# antennenanalysator_m4_1.net
KiCad netlist of a schematic drawn in EAGLE
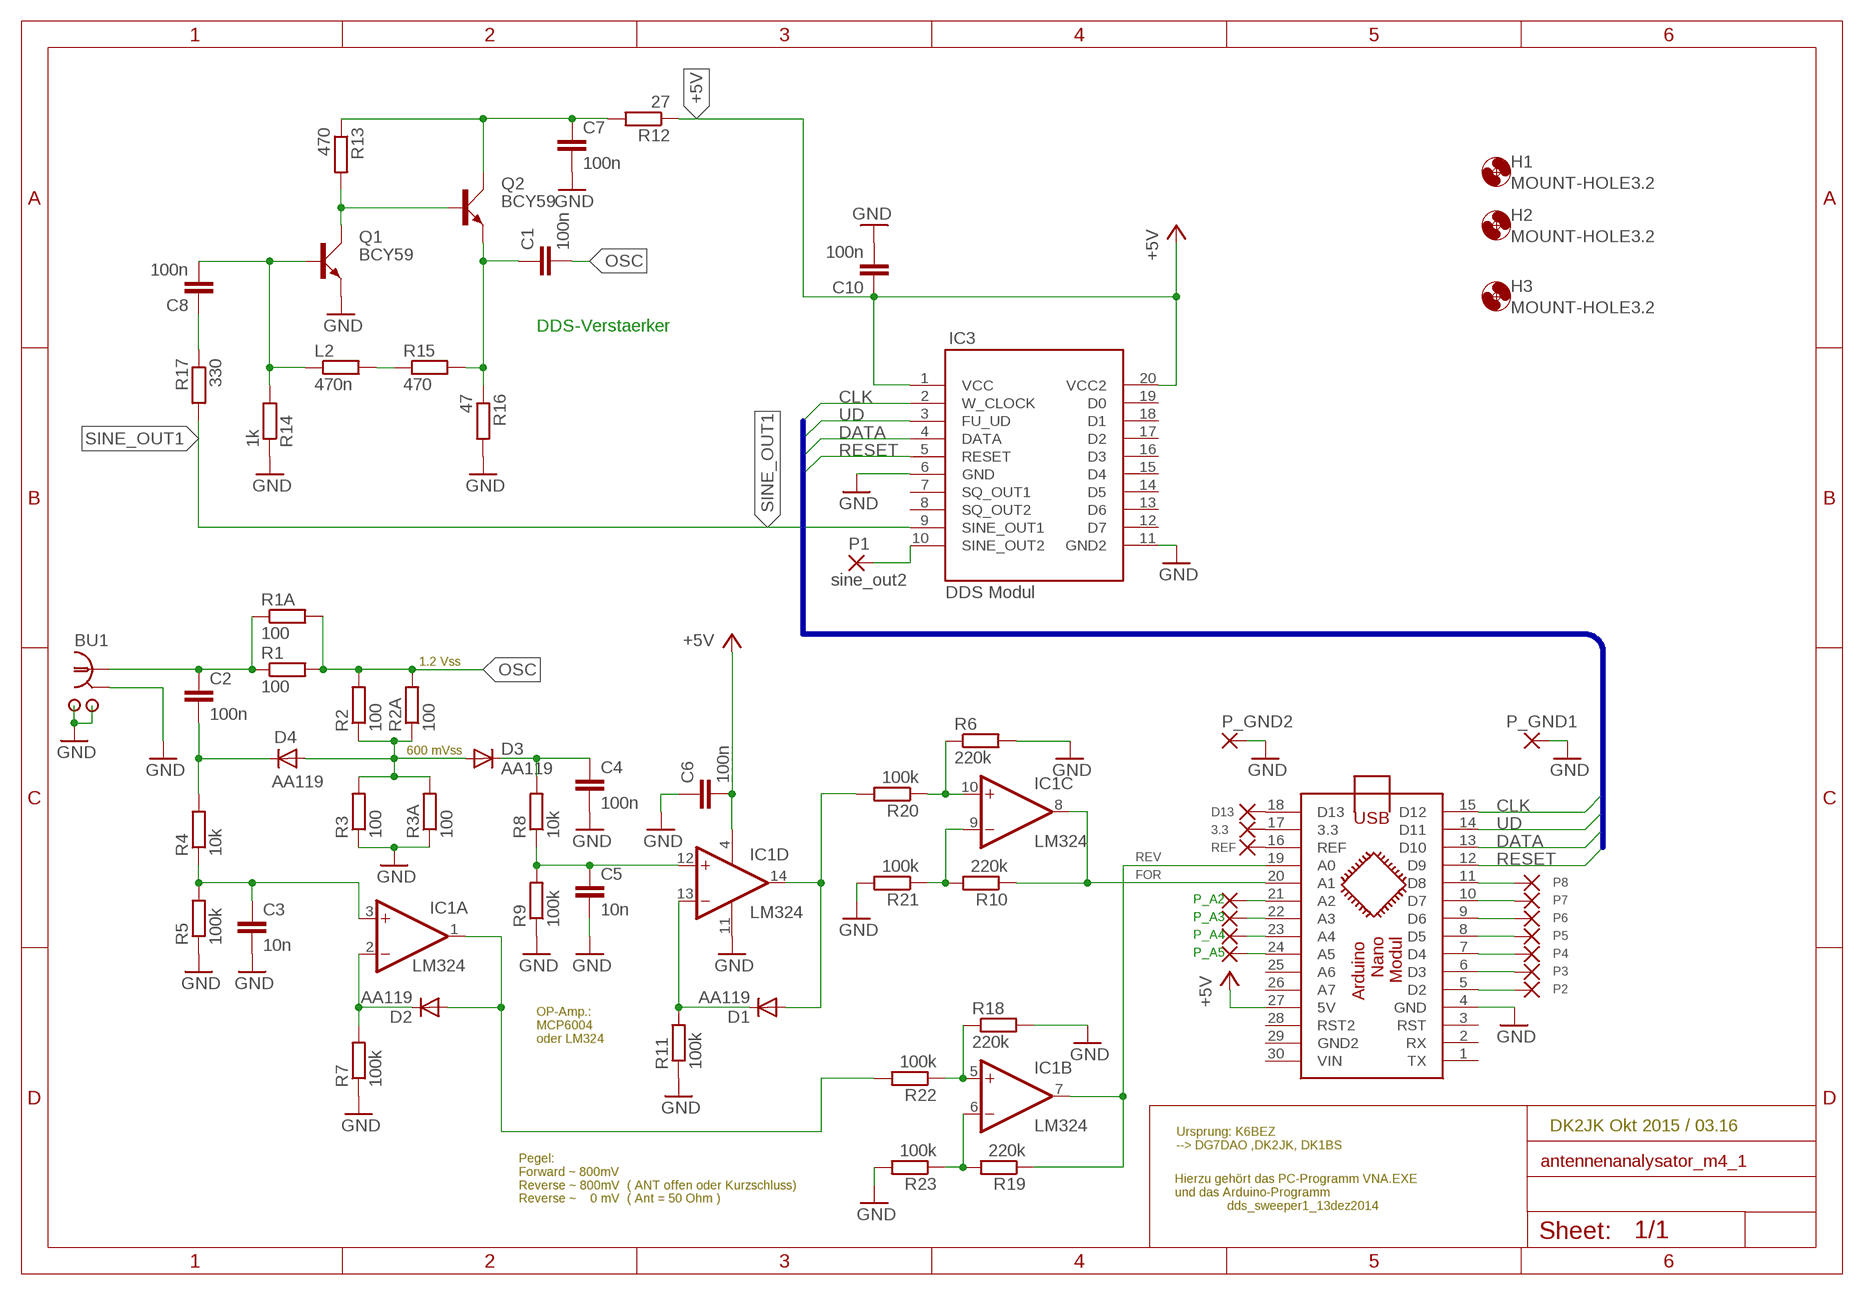
[diagram p0: schematic, sheet 1]

(export (version "E")
  (design (tool "Eeschema 10.0.6"))
  (components
    (comp (ref "3.3")
      (value "1,6/0,8")
      (footprint "eagle-import:1,6_0,8")
      (libsource (lib "eagle-import") (part "1,6/0,8"))
    )
    (comp (ref "ARDIUNO_NANO")
      (value "ARDUINO_NANO")
      (footprint "eagle-import:ARDUINO_NANO")
      (libsource (lib "eagle-import") (part "ARDUINO_NANO"))
    )
    (comp (ref "BU1")
      (value "BNC_1BNC_L")
      (footprint "eagle-import:BNC")
      (libsource (lib "eagle-import") (part "BNC_1BNC_L"))
    )
    (comp (ref "C1")
      (value "100n")
      (footprint "eagle-import:C025-025X050")
      (libsource (lib "eagle-import") (part "C-EU025-025X050"))
    )
    (comp (ref "C2")
      (value "100n")
      (footprint "eagle-import:C025-025X050")
      (libsource (lib "eagle-import") (part "C-EU025-025X050"))
    )
    (comp (ref "C3")
      (value "10n")
      (footprint "eagle-import:C025-025X050")
      (libsource (lib "eagle-import") (part "C-EU025-025X050"))
    )
    (comp (ref "C4")
      (value "100n")
      (footprint "eagle-import:C025-025X050")
      (libsource (lib "eagle-import") (part "C-EU025-025X050"))
    )
    (comp (ref "C5")
      (value "10n")
      (footprint "eagle-import:C025-025X050")
      (libsource (lib "eagle-import") (part "C-EU025-025X050"))
    )
    (comp (ref "C6")
      (value "100n")
      (footprint "eagle-import:C025-025X050")
      (libsource (lib "eagle-import") (part "C-EU025-025X050"))
    )
    (comp (ref "C7")
      (value "100n")
      (footprint "eagle-import:C025-025X050")
      (libsource (lib "eagle-import") (part "C-EU025-025X050"))
    )
    (comp (ref "C8")
      (value "100n")
      (footprint "eagle-import:C025-025X050")
      (libsource (lib "eagle-import") (part "C-EU025-025X050"))
    )
    (comp (ref "C10")
      (value "100n")
      (footprint "eagle-import:C025-025X050")
      (libsource (lib "eagle-import") (part "C-EU025-025X050"))
    )
    (comp (ref "D1")
      (value "AA119")
      (footprint "eagle-import:DO07")
      (libsource (lib "eagle-import") (part "AA119"))
    )
    (comp (ref "D2")
      (value "AA119")
      (footprint "eagle-import:DO07")
      (libsource (lib "eagle-import") (part "AA119"))
    )
    (comp (ref "D3")
      (value "AA119")
      (footprint "eagle-import:DO07")
      (libsource (lib "eagle-import") (part "AA119"))
    )
    (comp (ref "D4")
      (value "AA119")
      (footprint "eagle-import:DO07")
      (libsource (lib "eagle-import") (part "AA119"))
    )
    (comp (ref "D13")
      (value "1,6/0,8")
      (footprint "eagle-import:1,6_0,8")
      (libsource (lib "eagle-import") (part "1,6/0,8"))
    )
    (comp (ref "H1")
      (value "MOUNT-HOLE3.2")
      (footprint "eagle-import:3,2")
      (libsource (lib "eagle-import") (part "MOUNT-HOLE3.2"))
    )
    (comp (ref "H2")
      (value "MOUNT-HOLE3.2")
      (footprint "eagle-import:3,2")
      (libsource (lib "eagle-import") (part "MOUNT-HOLE3.2"))
    )
    (comp (ref "H3")
      (value "MOUNT-HOLE3.2")
      (footprint "eagle-import:3,2")
      (libsource (lib "eagle-import") (part "MOUNT-HOLE3.2"))
    )
    (comp (ref "IC1")
      (value "LM324")
      (footprint "eagle-import:DIL14")
      (libsource (lib "eagle-import") (part "LM324N"))
    )
    (comp (ref "IC3")
      (value "DDS Modul")
      (footprint "eagle-import:MODULE")
      (libsource (lib "eagle-import") (part "MODULE"))
    )
    (comp (ref "L2")
      (value "470n")
      (footprint "eagle-import:0207_10")
      (libsource (lib "eagle-import") (part "R-EU_0207/10"))
    )
    (comp (ref "P1")
      (value "sine_out2")
      (footprint "eagle-import:1,6_0,8")
      (libsource (lib "eagle-import") (part "1,6/0,8"))
    )
    (comp (ref "P2")
      (value "1,6/0,8")
      (footprint "eagle-import:1,6_0,8")
      (libsource (lib "eagle-import") (part "1,6/0,8"))
    )
    (comp (ref "P3")
      (value "1,6/0,8")
      (footprint "eagle-import:1,6_0,8")
      (libsource (lib "eagle-import") (part "1,6/0,8"))
    )
    (comp (ref "P4")
      (value "1,6/0,8")
      (footprint "eagle-import:1,6_0,8")
      (libsource (lib "eagle-import") (part "1,6/0,8"))
    )
    (comp (ref "P5")
      (value "1,6/0,8")
      (footprint "eagle-import:1,6_0,8")
      (libsource (lib "eagle-import") (part "1,6/0,8"))
    )
    (comp (ref "P6")
      (value "1,6/0,8")
      (footprint "eagle-import:1,6_0,8")
      (libsource (lib "eagle-import") (part "1,6/0,8"))
    )
    (comp (ref "P7")
      (value "1,6/0,8")
      (footprint "eagle-import:1,6_0,8")
      (libsource (lib "eagle-import") (part "1,6/0,8"))
    )
    (comp (ref "P8")
      (value "1,6/0,8")
      (footprint "eagle-import:1,6_0,8")
      (libsource (lib "eagle-import") (part "1,6/0,8"))
    )
    (comp (ref "P_A2")
      (value "1,6/0,8")
      (footprint "eagle-import:1,6_0,8")
      (libsource (lib "eagle-import") (part "1,6/0,8"))
    )
    (comp (ref "P_A3")
      (value "1,6/0,8")
      (footprint "eagle-import:1,6_0,8")
      (libsource (lib "eagle-import") (part "1,6/0,8"))
    )
    (comp (ref "P_A4")
      (value "1,6/0,8")
      (footprint "eagle-import:1,6_0,8")
      (libsource (lib "eagle-import") (part "1,6/0,8"))
    )
    (comp (ref "P_A5")
      (value "1,6/0,8")
      (footprint "eagle-import:1,6_0,8")
      (libsource (lib "eagle-import") (part "1,6/0,8"))
    )
    (comp (ref "P_GND1")
      (value "1,6/0,8")
      (footprint "eagle-import:1,6_0,8")
      (libsource (lib "eagle-import") (part "1,6/0,8"))
    )
    (comp (ref "P_GND2")
      (value "1,6/0,8")
      (footprint "eagle-import:1,6_0,8")
      (libsource (lib "eagle-import") (part "1,6/0,8"))
    )
    (comp (ref "Q1")
      (value "BCY59")
      (footprint "eagle-import:TO18A")
      (libsource (lib "eagle-import") (part "2N2222"))
    )
    (comp (ref "Q2")
      (value "BCY59")
      (footprint "eagle-import:TO18A")
      (libsource (lib "eagle-import") (part "2N2222"))
    )
    (comp (ref "R1")
      (value "100")
      (footprint "eagle-import:0207_10")
      (libsource (lib "eagle-import") (part "R-EU_0207/10"))
    )
    (comp (ref "R1A")
      (value "100")
      (footprint "eagle-import:0207_10")
      (libsource (lib "eagle-import") (part "R-EU_0207/10"))
    )
    (comp (ref "R2")
      (value "100")
      (footprint "eagle-import:0207_10")
      (libsource (lib "eagle-import") (part "R-EU_0207/10"))
    )
    (comp (ref "R2A")
      (value "100")
      (footprint "eagle-import:0207_10")
      (libsource (lib "eagle-import") (part "R-EU_0207/10"))
    )
    (comp (ref "R3")
      (value "100")
      (footprint "eagle-import:0207_10")
      (libsource (lib "eagle-import") (part "R-EU_0207/10"))
    )
    (comp (ref "R3A")
      (value "100")
      (footprint "eagle-import:0207_10")
      (libsource (lib "eagle-import") (part "R-EU_0207/10"))
    )
    (comp (ref "R4")
      (value "10k")
      (footprint "eagle-import:0207_10")
      (libsource (lib "eagle-import") (part "R-EU_0207/10"))
    )
    (comp (ref "R5")
      (value "100k")
      (footprint "eagle-import:0207_10")
      (libsource (lib "eagle-import") (part "R-EU_0207/10"))
    )
    (comp (ref "R6")
      (value "220k")
      (footprint "eagle-import:0207_10")
      (libsource (lib "eagle-import") (part "rcl_R-EU_0207/10"))
    )
    (comp (ref "R7")
      (value "100k")
      (footprint "eagle-import:0207_10")
      (libsource (lib "eagle-import") (part "R-EU_0207/10"))
    )
    (comp (ref "R8")
      (value "10k")
      (footprint "eagle-import:0207_10")
      (libsource (lib "eagle-import") (part "R-EU_0207/10"))
    )
    (comp (ref "R9")
      (value "100k")
      (footprint "eagle-import:0207_10")
      (libsource (lib "eagle-import") (part "R-EU_0207/10"))
    )
    (comp (ref "R10")
      (value "220k")
      (footprint "eagle-import:0207_10")
      (libsource (lib "eagle-import") (part "rcl_R-EU_0207/10"))
    )
    (comp (ref "R11")
      (value "100k")
      (footprint "eagle-import:0207_10")
      (libsource (lib "eagle-import") (part "R-EU_0207/10"))
    )
    (comp (ref "R12")
      (value "27")
      (footprint "eagle-import:0207_10")
      (libsource (lib "eagle-import") (part "R-EU_0207/10"))
    )
    (comp (ref "R13")
      (value "470")
      (footprint "eagle-import:0207_10")
      (libsource (lib "eagle-import") (part "R-EU_0207/10"))
    )
    (comp (ref "R14")
      (value "1k")
      (footprint "eagle-import:0207_10")
      (libsource (lib "eagle-import") (part "R-EU_0207/10"))
    )
    (comp (ref "R15")
      (value "470")
      (footprint "eagle-import:0207_10")
      (libsource (lib "eagle-import") (part "R-EU_0207/10"))
    )
    (comp (ref "R16")
      (value "47")
      (footprint "eagle-import:0207_10")
      (libsource (lib "eagle-import") (part "R-EU_0207/10"))
    )
    (comp (ref "R17")
      (value "330")
      (footprint "eagle-import:0207_10")
      (libsource (lib "eagle-import") (part "R-EU_0207/10"))
    )
    (comp (ref "R18")
      (value "220k")
      (footprint "eagle-import:0207_10")
      (libsource (lib "eagle-import") (part "rcl_R-EU_0207/10"))
    )
    (comp (ref "R19")
      (value "220k")
      (footprint "eagle-import:0207_10")
      (libsource (lib "eagle-import") (part "rcl_R-EU_0207/10"))
    )
    (comp (ref "R20")
      (value "100k")
      (footprint "eagle-import:0207_10")
      (libsource (lib "eagle-import") (part "R-EU_0207/10"))
    )
    (comp (ref "R21")
      (value "100k")
      (footprint "eagle-import:0207_10")
      (libsource (lib "eagle-import") (part "R-EU_0207/10"))
    )
    (comp (ref "R22")
      (value "100k")
      (footprint "eagle-import:0207_10")
      (libsource (lib "eagle-import") (part "R-EU_0207/10"))
    )
    (comp (ref "R23")
      (value "100k")
      (footprint "eagle-import:0207_10")
      (libsource (lib "eagle-import") (part "R-EU_0207/10"))
    )
    (comp (ref "REF")
      (value "1,6/0,8")
      (footprint "eagle-import:1,6_0,8")
      (libsource (lib "eagle-import") (part "1,6/0,8"))
    )
  )
  (nets
    (net (code "2") (name "+5V") (class "Default")
      (node (ref "ARDIUNO_NANO") (pin "27") (pinfunction "5V_27") (pintype "bidirectional"))
      (node (ref "C10") (pin "1") (pinfunction "1_1") (pintype "passive"))
      (node (ref "C6") (pin "2") (pinfunction "2_2") (pintype "passive"))
      (node (ref "IC1") (pin "4") (pinfunction "V+_4") (pintype "power_in"))
      (node (ref "IC3") (pin "1") (pinfunction "VCC_1") (pintype "power_in"))
      (node (ref "IC3") (pin "20") (pinfunction "VCC2_20") (pintype "power_in"))
      (node (ref "R12") (pin "1") (pinfunction "1_1") (pintype "passive"))
    )
    (net (code "3") (name "/CLK") (class "Default")
      (node (ref "ARDIUNO_NANO") (pin "15") (pinfunction "D12_15") (pintype "bidirectional"))
      (node (ref "IC3") (pin "2") (pinfunction "W_CLOCK_2") (pintype "input"))
    )
    (net (code "4") (name "/DATA") (class "Default")
      (node (ref "ARDIUNO_NANO") (pin "13") (pinfunction "D10_13") (pintype "bidirectional"))
      (node (ref "IC3") (pin "4") (pinfunction "DATA_4") (pintype "input"))
    )
    (net (code "5") (name "/FOR") (class "Default")
      (node (ref "ARDIUNO_NANO") (pin "20") (pinfunction "A1_20") (pintype "bidirectional"))
      (node (ref "IC1") (pin "8") (pinfunction "OUT_8") (pintype "output"))
      (node (ref "R10") (pin "1") (pinfunction "1_1") (pintype "passive"))
    )
    (net (code "6") (name "/RESET") (class "Default")
      (node (ref "ARDIUNO_NANO") (pin "12") (pinfunction "D9_12") (pintype "bidirectional"))
      (node (ref "IC3") (pin "5") (pinfunction "RESET_5") (pintype "input"))
    )
    (net (code "7") (name "/REV") (class "Default")
      (node (ref "ARDIUNO_NANO") (pin "19") (pinfunction "A0_19") (pintype "bidirectional"))
      (node (ref "IC1") (pin "7") (pinfunction "OUT_7") (pintype "output"))
      (node (ref "R19") (pin "1") (pinfunction "1_1") (pintype "passive"))
    )
    (net (code "8") (name "/UD") (class "Default")
      (node (ref "ARDIUNO_NANO") (pin "14") (pinfunction "D11_14") (pintype "bidirectional"))
      (node (ref "IC3") (pin "3") (pinfunction "FU_UD_3") (pintype "input"))
    )
    (net (code "10") (name "GND") (class "Default")
      (node (ref "ARDIUNO_NANO") (pin "4") (pinfunction "GND_4") (pintype "bidirectional"))
      (node (ref "BU1") (pin "GND") (pinfunction "GND_GND") (pintype "passive"))
      (node (ref "BU1") (pin "M1") (pinfunction "M1_M1") (pintype "passive"))
      (node (ref "BU1") (pin "M2") (pinfunction "M2_M2") (pintype "passive"))
      (node (ref "C10") (pin "2") (pinfunction "2_2") (pintype "passive"))
      (node (ref "C3") (pin "2") (pinfunction "2_2") (pintype "passive"))
      (node (ref "C4") (pin "2") (pinfunction "2_2") (pintype "passive"))
      (node (ref "C5") (pin "2") (pinfunction "2_2") (pintype "passive"))
      (node (ref "C6") (pin "1") (pinfunction "1_1") (pintype "passive"))
      (node (ref "C7") (pin "2") (pinfunction "2_2") (pintype "passive"))
      (node (ref "IC1") (pin "11") (pinfunction "V-_11") (pintype "power_in"))
      (node (ref "IC3") (pin "11") (pinfunction "GND2_11") (pintype "power_in"))
      (node (ref "IC3") (pin "6") (pinfunction "GND_6") (pintype "power_in"))
      (node (ref "P_GND1") (pin "1") (pinfunction "P_1") (pintype "passive"))
      (node (ref "P_GND2") (pin "1") (pinfunction "P_1") (pintype "passive"))
      (node (ref "Q1") (pin "E") (pinfunction "E_E") (pintype "passive"))
      (node (ref "R11") (pin "1") (pinfunction "1_1") (pintype "passive"))
      (node (ref "R14") (pin "1") (pinfunction "1_1") (pintype "passive"))
      (node (ref "R16") (pin "2") (pinfunction "2_2") (pintype "passive"))
      (node (ref "R18") (pin "2") (pinfunction "2_2") (pintype "passive"))
      (node (ref "R21") (pin "2") (pinfunction "2_2") (pintype "passive"))
      (node (ref "R23") (pin "2") (pinfunction "2_2") (pintype "passive"))
      (node (ref "R3") (pin "1") (pinfunction "1_1") (pintype "passive"))
      (node (ref "R3A") (pin "1") (pinfunction "1_1") (pintype "passive"))
      (node (ref "R5") (pin "1") (pinfunction "1_1") (pintype "passive"))
      (node (ref "R6") (pin "2") (pinfunction "2_2") (pintype "passive"))
      (node (ref "R7") (pin "1") (pinfunction "1_1") (pintype "passive"))
      (node (ref "R9") (pin "1") (pinfunction "1_1") (pintype "passive"))
    )
    (net (code "11") (name "Net-(3.3-P)") (class "Default")
      (node (ref "3.3") (pin "1") (pinfunction "P_1") (pintype "passive"))
      (node (ref "ARDIUNO_NANO") (pin "17") (pinfunction "3.3_17") (pintype "bidirectional"))
    )
    (net (code "12") (name "Net-(ARDIUNO_NANO-A2)") (class "Default")
      (node (ref "ARDIUNO_NANO") (pin "21") (pinfunction "A2_21") (pintype "bidirectional"))
      (node (ref "P_A2") (pin "1") (pinfunction "P_1") (pintype "passive"))
    )
    (net (code "13") (name "Net-(ARDIUNO_NANO-A3)") (class "Default")
      (node (ref "ARDIUNO_NANO") (pin "22") (pinfunction "A3_22") (pintype "bidirectional"))
      (node (ref "P_A3") (pin "1") (pinfunction "P_1") (pintype "passive"))
    )
    (net (code "14") (name "Net-(ARDIUNO_NANO-A4)") (class "Default")
      (node (ref "ARDIUNO_NANO") (pin "23") (pinfunction "A4_23") (pintype "bidirectional"))
      (node (ref "P_A4") (pin "1") (pinfunction "P_1") (pintype "passive"))
    )
    (net (code "15") (name "Net-(ARDIUNO_NANO-A5)") (class "Default")
      (node (ref "ARDIUNO_NANO") (pin "24") (pinfunction "A5_24") (pintype "bidirectional"))
      (node (ref "P_A5") (pin "1") (pinfunction "P_1") (pintype "passive"))
    )
    (net (code "16") (name "Net-(ARDIUNO_NANO-D2)") (class "Default")
      (node (ref "ARDIUNO_NANO") (pin "5") (pinfunction "D2_5") (pintype "bidirectional"))
      (node (ref "P2") (pin "1") (pinfunction "P_1") (pintype "passive"))
    )
    (net (code "17") (name "Net-(ARDIUNO_NANO-D3)") (class "Default")
      (node (ref "ARDIUNO_NANO") (pin "6") (pinfunction "D3_6") (pintype "bidirectional"))
      (node (ref "P3") (pin "1") (pinfunction "P_1") (pintype "passive"))
    )
    (net (code "18") (name "Net-(ARDIUNO_NANO-D4)") (class "Default")
      (node (ref "ARDIUNO_NANO") (pin "7") (pinfunction "D4_7") (pintype "bidirectional"))
      (node (ref "P4") (pin "1") (pinfunction "P_1") (pintype "passive"))
    )
    (net (code "19") (name "Net-(ARDIUNO_NANO-D5)") (class "Default")
      (node (ref "ARDIUNO_NANO") (pin "8") (pinfunction "D5_8") (pintype "bidirectional"))
      (node (ref "P5") (pin "1") (pinfunction "P_1") (pintype "passive"))
    )
    (net (code "20") (name "Net-(ARDIUNO_NANO-D6)") (class "Default")
      (node (ref "ARDIUNO_NANO") (pin "9") (pinfunction "D6_9") (pintype "bidirectional"))
      (node (ref "P6") (pin "1") (pinfunction "P_1") (pintype "passive"))
    )
    (net (code "21") (name "Net-(ARDIUNO_NANO-D7)") (class "Default")
      (node (ref "ARDIUNO_NANO") (pin "10") (pinfunction "D7_10") (pintype "bidirectional"))
      (node (ref "P7") (pin "1") (pinfunction "P_1") (pintype "passive"))
    )
    (net (code "22") (name "Net-(ARDIUNO_NANO-D8)") (class "Default")
      (node (ref "ARDIUNO_NANO") (pin "11") (pinfunction "D8_11") (pintype "bidirectional"))
      (node (ref "P8") (pin "1") (pinfunction "P_1") (pintype "passive"))
    )
    (net (code "23") (name "Net-(ARDIUNO_NANO-D13)") (class "Default")
      (node (ref "ARDIUNO_NANO") (pin "18") (pinfunction "D13_18") (pintype "bidirectional"))
      (node (ref "D13") (pin "1") (pinfunction "P_1") (pintype "passive"))
    )
    (net (code "24") (name "Net-(ARDIUNO_NANO-REF)") (class "Default")
      (node (ref "ARDIUNO_NANO") (pin "16") (pinfunction "REF_16") (pintype "bidirectional"))
      (node (ref "REF") (pin "1") (pinfunction "P_1") (pintype "passive"))
    )
    (net (code "25") (name "Net-(BU1-SEELE)") (class "Default")
      (node (ref "BU1") (pin "SIGNAL") (pinfunction "SEELE_SIGNAL") (pintype "passive"))
      (node (ref "C2") (pin "1") (pinfunction "1_1") (pintype "passive"))
      (node (ref "R1") (pin "1") (pinfunction "1_1") (pintype "passive"))
      (node (ref "R1A") (pin "1") (pinfunction "1_1") (pintype "passive"))
    )
    (net (code "26") (name "Net-(C1-Pad1)") (class "Default")
      (node (ref "C1") (pin "1") (pinfunction "1_1") (pintype "passive"))
      (node (ref "Q2") (pin "E") (pinfunction "E_E") (pintype "passive"))
      (node (ref "R15") (pin "2") (pinfunction "2_2") (pintype "passive"))
      (node (ref "R16") (pin "1") (pinfunction "1_1") (pintype "passive"))
    )
    (net (code "27") (name "Net-(C2-Pad2)") (class "Default")
      (node (ref "C2") (pin "2") (pinfunction "2_2") (pintype "passive"))
      (node (ref "D4") (pin "C") (pinfunction "C_C") (pintype "passive"))
      (node (ref "R4") (pin "2") (pinfunction "2_2") (pintype "passive"))
    )
    (net (code "28") (name "Net-(C4-Pad1)") (class "Default")
      (node (ref "C4") (pin "1") (pinfunction "1_1") (pintype "passive"))
      (node (ref "D3") (pin "C") (pinfunction "C_C") (pintype "passive"))
      (node (ref "R8") (pin "2") (pinfunction "2_2") (pintype "passive"))
    )
    (net (code "29") (name "Net-(C7-Pad1)") (class "Default")
      (node (ref "C7") (pin "1") (pinfunction "1_1") (pintype "passive"))
      (node (ref "Q2") (pin "C") (pinfunction "C_C") (pintype "passive"))
      (node (ref "R12") (pin "2") (pinfunction "2_2") (pintype "passive"))
      (node (ref "R13") (pin "1") (pinfunction "1_1") (pintype "passive"))
    )
    (net (code "30") (name "Net-(C8-Pad1)") (class "Default")
      (node (ref "C8") (pin "1") (pinfunction "1_1") (pintype "passive"))
      (node (ref "R17") (pin "1") (pinfunction "1_1") (pintype "passive"))
    )
    (net (code "31") (name "Net-(C8-Pad2)") (class "Default")
      (node (ref "C8") (pin "2") (pinfunction "2_2") (pintype "passive"))
      (node (ref "L2") (pin "1") (pinfunction "1_1") (pintype "passive"))
      (node (ref "Q1") (pin "B") (pinfunction "B_B") (pintype "passive"))
      (node (ref "R14") (pin "2") (pinfunction "2_2") (pintype "passive"))
    )
    (net (code "32") (name "Net-(D3-PadA)") (class "Default")
      (node (ref "D3") (pin "A") (pinfunction "A_A") (pintype "passive"))
      (node (ref "D4") (pin "A") (pinfunction "A_A") (pintype "passive"))
      (node (ref "R2") (pin "1") (pinfunction "1_1") (pintype "passive"))
      (node (ref "R2A") (pin "1") (pinfunction "1_1") (pintype "passive"))
      (node (ref "R3") (pin "2") (pinfunction "2_2") (pintype "passive"))
      (node (ref "R3A") (pin "2") (pinfunction "2_2") (pintype "passive"))
    )
    (net (code "33") (name "Net-(IC1A-+IN)") (class "Default")
      (node (ref "C3") (pin "1") (pinfunction "1_1") (pintype "passive"))
      (node (ref "IC1") (pin "3") (pinfunction "+IN_3") (pintype "input"))
      (node (ref "R4") (pin "1") (pinfunction "1_1") (pintype "passive"))
      (node (ref "R5") (pin "2") (pinfunction "2_2") (pintype "passive"))
    )
    (net (code "34") (name "Net-(IC1A--IN)") (class "Default")
      (node (ref "D2") (pin "C") (pinfunction "C_C") (pintype "passive"))
      (node (ref "IC1") (pin "2") (pinfunction "-IN_2") (pintype "input"))
      (node (ref "R7") (pin "2") (pinfunction "2_2") (pintype "passive"))
    )
    (net (code "35") (name "Net-(IC1A-OUT)") (class "Default")
      (node (ref "D2") (pin "A") (pinfunction "A_A") (pintype "passive"))
      (node (ref "IC1") (pin "1") (pinfunction "OUT_1") (pintype "output"))
      (node (ref "R22") (pin "2") (pinfunction "2_2") (pintype "passive"))
    )
    (net (code "36") (name "Net-(IC1B-+IN)") (class "Default")
      (node (ref "IC1") (pin "5") (pinfunction "+IN_5") (pintype "input"))
      (node (ref "R18") (pin "1") (pinfunction "1_1") (pintype "passive"))
      (node (ref "R22") (pin "1") (pinfunction "1_1") (pintype "passive"))
    )
    (net (code "37") (name "Net-(IC1B--IN)") (class "Default")
      (node (ref "IC1") (pin "6") (pinfunction "-IN_6") (pintype "input"))
      (node (ref "R19") (pin "2") (pinfunction "2_2") (pintype "passive"))
      (node (ref "R23") (pin "1") (pinfunction "1_1") (pintype "passive"))
    )
    (net (code "38") (name "Net-(IC1C-+IN)") (class "Default")
      (node (ref "IC1") (pin "10") (pinfunction "+IN_10") (pintype "input"))
      (node (ref "R20") (pin "1") (pinfunction "1_1") (pintype "passive"))
      (node (ref "R6") (pin "1") (pinfunction "1_1") (pintype "passive"))
    )
    (net (code "39") (name "Net-(IC1C--IN)") (class "Default")
      (node (ref "IC1") (pin "9") (pinfunction "-IN_9") (pintype "input"))
      (node (ref "R10") (pin "2") (pinfunction "2_2") (pintype "passive"))
      (node (ref "R21") (pin "1") (pinfunction "1_1") (pintype "passive"))
    )
    (net (code "40") (name "Net-(IC1D-+IN)") (class "Default")
      (node (ref "C5") (pin "1") (pinfunction "1_1") (pintype "passive"))
      (node (ref "IC1") (pin "12") (pinfunction "+IN_12") (pintype "input"))
      (node (ref "R8") (pin "1") (pinfunction "1_1") (pintype "passive"))
      (node (ref "R9") (pin "2") (pinfunction "2_2") (pintype "passive"))
    )
    (net (code "41") (name "Net-(IC1D--IN)") (class "Default")
      (node (ref "D1") (pin "C") (pinfunction "C_C") (pintype "passive"))
      (node (ref "IC1") (pin "13") (pinfunction "-IN_13") (pintype "input"))
      (node (ref "R11") (pin "2") (pinfunction "2_2") (pintype "passive"))
    )
    (net (code "42") (name "Net-(IC1D-OUT)") (class "Default")
      (node (ref "D1") (pin "A") (pinfunction "A_A") (pintype "passive"))
      (node (ref "IC1") (pin "14") (pinfunction "OUT_14") (pintype "output"))
      (node (ref "R20") (pin "2") (pinfunction "2_2") (pintype "passive"))
    )
    (net (code "43") (name "Net-(IC3-SINE_OUT2)") (class "Default")
      (node (ref "IC3") (pin "10") (pinfunction "SINE_OUT2_10") (pintype "output"))
      (node (ref "P1") (pin "1") (pinfunction "P_1") (pintype "passive"))
    )
    (net (code "44") (name "Net-(L2-Pad2)") (class "Default")
      (node (ref "L2") (pin "2") (pinfunction "2_2") (pintype "passive"))
      (node (ref "R15") (pin "1") (pinfunction "1_1") (pintype "passive"))
    )
    (net (code "45") (name "Net-(Q1-PadC)") (class "Default")
      (node (ref "Q1") (pin "C") (pinfunction "C_C") (pintype "passive"))
      (node (ref "Q2") (pin "B") (pinfunction "B_B") (pintype "passive"))
      (node (ref "R13") (pin "2") (pinfunction "2_2") (pintype "passive"))
    )
    (net (code "46") (name "OSC") (class "Default")
      (node (ref "C1") (pin "2") (pinfunction "2_2") (pintype "passive"))
      (node (ref "R1") (pin "2") (pinfunction "2_2") (pintype "passive"))
      (node (ref "R1A") (pin "2") (pinfunction "2_2") (pintype "passive"))
      (node (ref "R2") (pin "2") (pinfunction "2_2") (pintype "passive"))
      (node (ref "R2A") (pin "2") (pinfunction "2_2") (pintype "passive"))
    )
    (net (code "47") (name "SINE_OUT1") (class "Default")
      (node (ref "IC3") (pin "9") (pinfunction "SINE_OUT1_9") (pintype "output"))
      (node (ref "R17") (pin "2") (pinfunction "2_2") (pintype "passive"))
    )
    (net (code "48") (name "unconnected-(ARDIUNO_NANO-A6-Pad25)") (class "Default")
      (node (ref "ARDIUNO_NANO") (pin "25") (pinfunction "A6_25") (pintype "bidirectional"))
    )
    (net (code "49") (name "unconnected-(ARDIUNO_NANO-A7-Pad26)") (class "Default")
      (node (ref "ARDIUNO_NANO") (pin "26") (pinfunction "A7_26") (pintype "bidirectional"))
    )
    (net (code "50") (name "unconnected-(ARDIUNO_NANO-GND2-Pad29)") (class "Default")
      (node (ref "ARDIUNO_NANO") (pin "29") (pinfunction "GND2_29") (pintype "bidirectional"))
    )
    (net (code "51") (name "unconnected-(ARDIUNO_NANO-RST-Pad3)") (class "Default")
      (node (ref "ARDIUNO_NANO") (pin "3") (pinfunction "RST_3") (pintype "bidirectional"))
    )
    (net (code "52") (name "unconnected-(ARDIUNO_NANO-RST2-Pad28)") (class "Default")
      (node (ref "ARDIUNO_NANO") (pin "28") (pinfunction "RST2_28") (pintype "bidirectional"))
    )
    (net (code "53") (name "unconnected-(ARDIUNO_NANO-RX-Pad2)") (class "Default")
      (node (ref "ARDIUNO_NANO") (pin "2") (pinfunction "RX_2") (pintype "bidirectional"))
    )
    (net (code "54") (name "unconnected-(ARDIUNO_NANO-TX-Pad1)") (class "Default")
      (node (ref "ARDIUNO_NANO") (pin "1") (pinfunction "TX_1") (pintype "bidirectional"))
    )
    (net (code "55") (name "unconnected-(ARDIUNO_NANO-VIN-Pad30)") (class "Default")
      (node (ref "ARDIUNO_NANO") (pin "30") (pinfunction "VIN_30") (pintype "bidirectional"))
    )
    (net (code "56") (name "unconnected-(IC3-D0-Pad19)") (class "Default")
      (node (ref "IC3") (pin "19") (pinfunction "D0_19") (pintype "input"))
    )
    (net (code "57") (name "unconnected-(IC3-D1-Pad18)") (class "Default")
      (node (ref "IC3") (pin "18") (pinfunction "D1_18") (pintype "input"))
    )
    (net (code "58") (name "unconnected-(IC3-D2-Pad17)") (class "Default")
      (node (ref "IC3") (pin "17") (pinfunction "D2_17") (pintype "input"))
    )
    (net (code "59") (name "unconnected-(IC3-D3-Pad16)") (class "Default")
      (node (ref "IC3") (pin "16") (pinfunction "D3_16") (pintype "input"))
    )
    (net (code "60") (name "unconnected-(IC3-D4-Pad15)") (class "Default")
      (node (ref "IC3") (pin "15") (pinfunction "D4_15") (pintype "input"))
    )
    (net (code "61") (name "unconnected-(IC3-D5-Pad14)") (class "Default")
      (node (ref "IC3") (pin "14") (pinfunction "D5_14") (pintype "input"))
    )
    (net (code "62") (name "unconnected-(IC3-D6-Pad13)") (class "Default")
      (node (ref "IC3") (pin "13") (pinfunction "D6_13") (pintype "input"))
    )
    (net (code "63") (name "unconnected-(IC3-D7-Pad12)") (class "Default")
      (node (ref "IC3") (pin "12") (pinfunction "D7_12") (pintype "input"))
    )
    (net (code "64") (name "unconnected-(IC3-SQ_OUT1-Pad7)") (class "Default")
      (node (ref "IC3") (pin "7") (pinfunction "SQ_OUT1_7") (pintype "output"))
    )
    (net (code "65") (name "unconnected-(IC3-SQ_OUT2-Pad8)") (class "Default")
      (node (ref "IC3") (pin "8") (pinfunction "SQ_OUT2_8") (pintype "output"))
    )
  )
)
